# 6WP_twelite_sensor.net
KiCad netlist of a schematic drawn in EAGLE
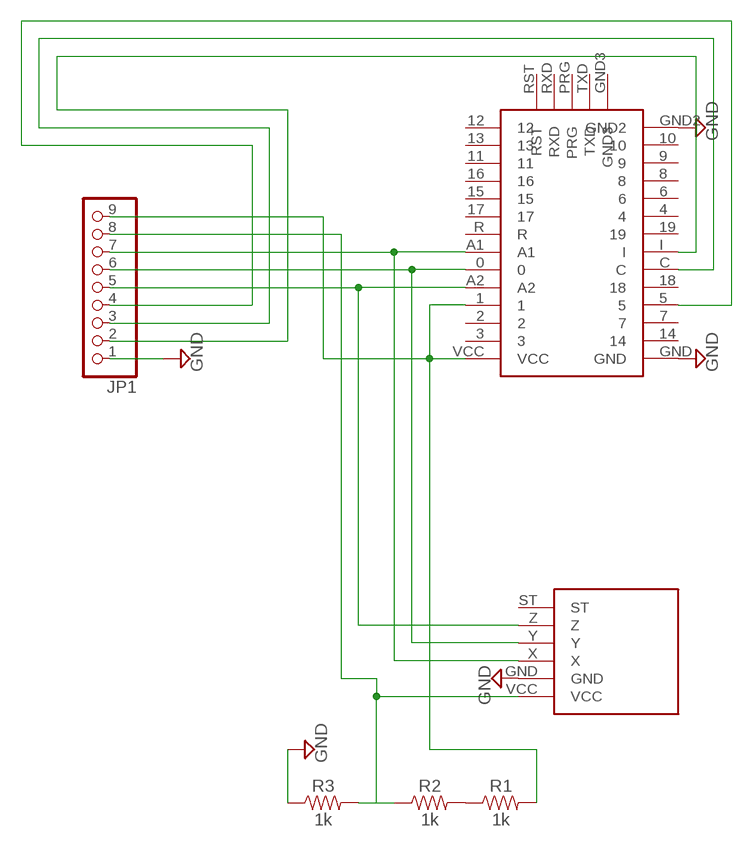
[diagram p0: schematic, sheet 1]

(export (version "E")
  (design (tool "Eeschema 10.0.6"))
  (components
    (comp (ref "A2")
      (value "ADXL335")
      (footprint "eagle-import:ADXL335")
      (libsource (lib "eagle-import") (part "ADXL335"))
    )
    (comp (ref "A4")
      (value "TWELITEDIP")
      (footprint "eagle-import:TWELITEDIP")
      (libsource (lib "eagle-import") (part "TWELITEDIP"))
    )
    (comp (ref "JP1")
      (value "PINHD-1X9/90")
      (footprint "eagle-import:1X09_90")
      (libsource (lib "eagle-import") (part "PINHD-1X9/90"))
    )
    (comp (ref "R1")
      (value "1k")
      (footprint "eagle-import:AXIAL-0.3")
      (libsource (lib "eagle-import") (part "1KOHM-HORIZ-1/4W-1%"))
    )
    (comp (ref "R2")
      (value "1k")
      (footprint "eagle-import:AXIAL-0.3")
      (libsource (lib "eagle-import") (part "1KOHM-HORIZ-1/4W-1%"))
    )
    (comp (ref "R3")
      (value "1k")
      (footprint "eagle-import:AXIAL-0.3")
      (libsource (lib "eagle-import") (part "1KOHM-HORIZ-1/4W-1%"))
    )
  )
  (nets
    (net (code "1") (name "GND") (class "Default")
      (node (ref "A2") (pin "GND") (pinfunction "GND_GND") (pintype "bidirectional"))
      (node (ref "A4") (pin "GND") (pinfunction "GND_GND") (pintype "bidirectional"))
      (node (ref "A4") (pin "GND2") (pinfunction "GND2_GND2") (pintype "bidirectional"))
      (node (ref "JP1") (pin "1") (pinfunction "1_1") (pintype "passive"))
      (node (ref "R3") (pin "P$1") (pinfunction "1_P$1") (pintype "passive"))
    )
    (net (code "2") (name "Net-(A2-PadX)") (class "Default")
      (node (ref "A2") (pin "X") (pinfunction "X_X") (pintype "bidirectional"))
      (node (ref "A4") (pin "A1") (pinfunction "A1_A1") (pintype "bidirectional"))
      (node (ref "JP1") (pin "7") (pinfunction "7_7") (pintype "passive"))
    )
    (net (code "3") (name "Net-(A2-PadY)") (class "Default")
      (node (ref "A2") (pin "Y") (pinfunction "Y_Y") (pintype "bidirectional"))
      (node (ref "A4") (pin "0") (pinfunction "0_0") (pintype "bidirectional"))
      (node (ref "JP1") (pin "6") (pinfunction "6_6") (pintype "passive"))
    )
    (net (code "4") (name "Net-(A2-PadZ)") (class "Default")
      (node (ref "A2") (pin "Z") (pinfunction "Z_Z") (pintype "bidirectional"))
      (node (ref "A4") (pin "A2") (pinfunction "A2_A2") (pintype "bidirectional"))
      (node (ref "JP1") (pin "5") (pinfunction "5_5") (pintype "passive"))
    )
    (net (code "5") (name "Net-(A4-Pad5)") (class "Default")
      (node (ref "A4") (pin "5") (pinfunction "5_5") (pintype "bidirectional"))
      (node (ref "JP1") (pin "4") (pinfunction "4_4") (pintype "passive"))
    )
    (net (code "6") (name "Net-(A4-PadC)") (class "Default")
      (node (ref "A4") (pin "C") (pinfunction "C_C") (pintype "bidirectional"))
      (node (ref "JP1") (pin "3") (pinfunction "3_3") (pintype "passive"))
    )
    (net (code "7") (name "Net-(A4-PadI)") (class "Default")
      (node (ref "A4") (pin "I") (pinfunction "I_I") (pintype "bidirectional"))
      (node (ref "JP1") (pin "2") (pinfunction "2_2") (pintype "passive"))
    )
    (net (code "8") (name "Net-(R1-1)") (class "Default")
      (node (ref "R1") (pin "P$1") (pinfunction "1_P$1") (pintype "passive"))
      (node (ref "R2") (pin "P$2") (pinfunction "2_P$2") (pintype "passive"))
    )
    (net (code "9") (name "Net-(R1-2)") (class "Default")
      (node (ref "A4") (pin "1") (pinfunction "1_1") (pintype "bidirectional"))
      (node (ref "A4") (pin "VCC") (pinfunction "VCC_VCC") (pintype "bidirectional"))
      (node (ref "JP1") (pin "9") (pinfunction "9_9") (pintype "passive"))
      (node (ref "R1") (pin "P$2") (pinfunction "2_P$2") (pintype "passive"))
    )
    (net (code "10") (name "Net-(R2-1)") (class "Default")
      (node (ref "A2") (pin "VCC") (pinfunction "VCC_VCC") (pintype "bidirectional"))
      (node (ref "JP1") (pin "8") (pinfunction "8_8") (pintype "passive"))
      (node (ref "R2") (pin "P$1") (pinfunction "1_P$1") (pintype "passive"))
      (node (ref "R3") (pin "P$2") (pinfunction "2_P$2") (pintype "passive"))
    )
    (net (code "11") (name "unconnected-(A2-PadST)") (class "Default")
      (node (ref "A2") (pin "ST") (pinfunction "ST_ST") (pintype "bidirectional"))
    )
    (net (code "12") (name "unconnected-(A4-Pad2)") (class "Default")
      (node (ref "A4") (pin "2") (pinfunction "2_2") (pintype "bidirectional"))
    )
    (net (code "13") (name "unconnected-(A4-Pad3)") (class "Default")
      (node (ref "A4") (pin "3") (pinfunction "3_3") (pintype "bidirectional"))
    )
    (net (code "14") (name "unconnected-(A4-Pad4)") (class "Default")
      (node (ref "A4") (pin "4") (pinfunction "4_4") (pintype "bidirectional"))
    )
    (net (code "15") (name "unconnected-(A4-Pad6)") (class "Default")
      (node (ref "A4") (pin "6") (pinfunction "6_6") (pintype "bidirectional"))
    )
    (net (code "16") (name "unconnected-(A4-Pad7)") (class "Default")
      (node (ref "A4") (pin "7") (pinfunction "7_7") (pintype "bidirectional"))
    )
    (net (code "17") (name "unconnected-(A4-Pad8)") (class "Default")
      (node (ref "A4") (pin "8") (pinfunction "8_8") (pintype "bidirectional"))
    )
    (net (code "18") (name "unconnected-(A4-Pad9)") (class "Default")
      (node (ref "A4") (pin "9") (pinfunction "9_9") (pintype "bidirectional"))
    )
    (net (code "19") (name "unconnected-(A4-Pad10)") (class "Default")
      (node (ref "A4") (pin "10") (pinfunction "10_10") (pintype "bidirectional"))
    )
    (net (code "20") (name "unconnected-(A4-Pad11)") (class "Default")
      (node (ref "A4") (pin "11") (pinfunction "11_11") (pintype "bidirectional"))
    )
    (net (code "21") (name "unconnected-(A4-Pad12)") (class "Default")
      (node (ref "A4") (pin "12") (pinfunction "12_12") (pintype "bidirectional"))
    )
    (net (code "22") (name "unconnected-(A4-Pad13)") (class "Default")
      (node (ref "A4") (pin "13") (pinfunction "13_13") (pintype "bidirectional"))
    )
    (net (code "23") (name "unconnected-(A4-Pad14)") (class "Default")
      (node (ref "A4") (pin "14") (pinfunction "14_14") (pintype "bidirectional"))
    )
    (net (code "24") (name "unconnected-(A4-Pad15)") (class "Default")
      (node (ref "A4") (pin "15") (pinfunction "15_15") (pintype "bidirectional"))
    )
    (net (code "25") (name "unconnected-(A4-Pad16)") (class "Default")
      (node (ref "A4") (pin "16") (pinfunction "16_16") (pintype "bidirectional"))
    )
    (net (code "26") (name "unconnected-(A4-Pad17)") (class "Default")
      (node (ref "A4") (pin "17") (pinfunction "17_17") (pintype "bidirectional"))
    )
    (net (code "27") (name "unconnected-(A4-Pad18)") (class "Default")
      (node (ref "A4") (pin "18") (pinfunction "18_18") (pintype "bidirectional"))
    )
    (net (code "28") (name "unconnected-(A4-Pad19)") (class "Default")
      (node (ref "A4") (pin "19") (pinfunction "19_19") (pintype "bidirectional"))
    )
    (net (code "29") (name "unconnected-(A4-PadGND3)") (class "Default")
      (node (ref "A4") (pin "GND3") (pinfunction "GND3_GND3") (pintype "bidirectional"))
    )
    (net (code "30") (name "unconnected-(A4-PadPRG)") (class "Default")
      (node (ref "A4") (pin "PRG") (pinfunction "PRG_PRG") (pintype "bidirectional"))
    )
    (net (code "31") (name "unconnected-(A4-PadR)") (class "Default")
      (node (ref "A4") (pin "R") (pinfunction "R_R") (pintype "bidirectional"))
    )
    (net (code "32") (name "unconnected-(A4-PadRST)") (class "Default")
      (node (ref "A4") (pin "RST") (pinfunction "RST_RST") (pintype "bidirectional"))
    )
    (net (code "33") (name "unconnected-(A4-PadRXD)") (class "Default")
      (node (ref "A4") (pin "RXD") (pinfunction "RXD_RXD") (pintype "bidirectional"))
    )
    (net (code "34") (name "unconnected-(A4-PadTXD)") (class "Default")
      (node (ref "A4") (pin "TXD") (pinfunction "TXD_TXD") (pintype "bidirectional"))
    )
  )
)
